# 1_27to2_54.net
KiCad netlist of a schematic drawn in Altium Designer
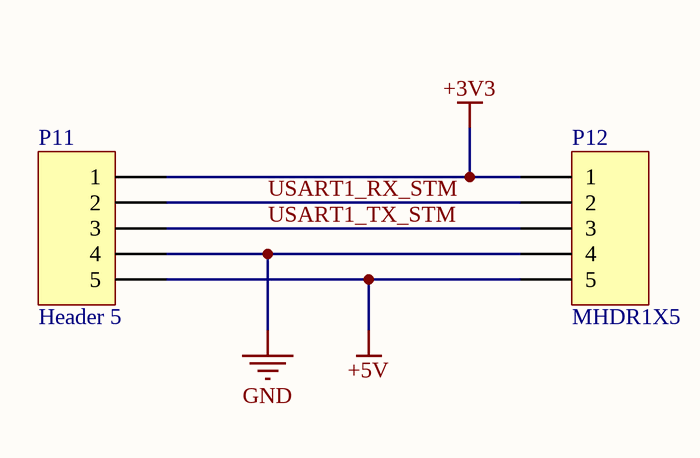
[diagram p0: 1.27to2.54.SchDoc]

(export (version "E")
  (design (tool "Eeschema 10.0.6"))
  (components
    (comp (ref "P11")
      (value "Header 5")
      (footprint "HDR1X5")
      (description "Header, 5-Pin")
      (fields (field (name "PUBLISHER") "Altium Limited"))
      (libsource (lib "Miscellaneous Connectors") (part "Header 5"))
    )
    (comp (ref "P12")
      (value "MHDR1X5")
      (footprint "MHDR1X5")
      (description "Header, 5-Pin")
      (fields (field (name "PUBLISHER") "Altium Limited"))
      (libsource (lib "Miscellaneous Connectors") (part "MHDR1X5"))
    )
  )
  (nets
    (net (code "1") (name "+3V3") (class "Default")
      (node (ref "P11") (pin "1") (pinfunction "1_1") (pintype "passive"))
      (node (ref "P12") (pin "1") (pinfunction "1_1") (pintype "passive"))
    )
    (net (code "2") (name "+5V") (class "Default")
      (node (ref "P11") (pin "5") (pinfunction "5_5") (pintype "passive"))
      (node (ref "P12") (pin "5") (pinfunction "5_5") (pintype "passive"))
    )
    (net (code "3") (name "/USART1_RX_STM") (class "Default")
      (node (ref "P11") (pin "2") (pinfunction "2_2") (pintype "passive"))
      (node (ref "P12") (pin "2") (pinfunction "2_2") (pintype "passive"))
    )
    (net (code "4") (name "/USART1_TX_STM") (class "Default")
      (node (ref "P11") (pin "3") (pinfunction "3_3") (pintype "passive"))
      (node (ref "P12") (pin "3") (pinfunction "3_3") (pintype "passive"))
    )
    (net (code "5") (name "GND") (class "Default")
      (node (ref "P11") (pin "4") (pinfunction "4_4") (pintype "passive"))
      (node (ref "P12") (pin "4") (pinfunction "4_4") (pintype "passive"))
    )
  )
)
